# bluz_proto_v2_revA.net
KiCad netlist of a schematic drawn in EAGLE
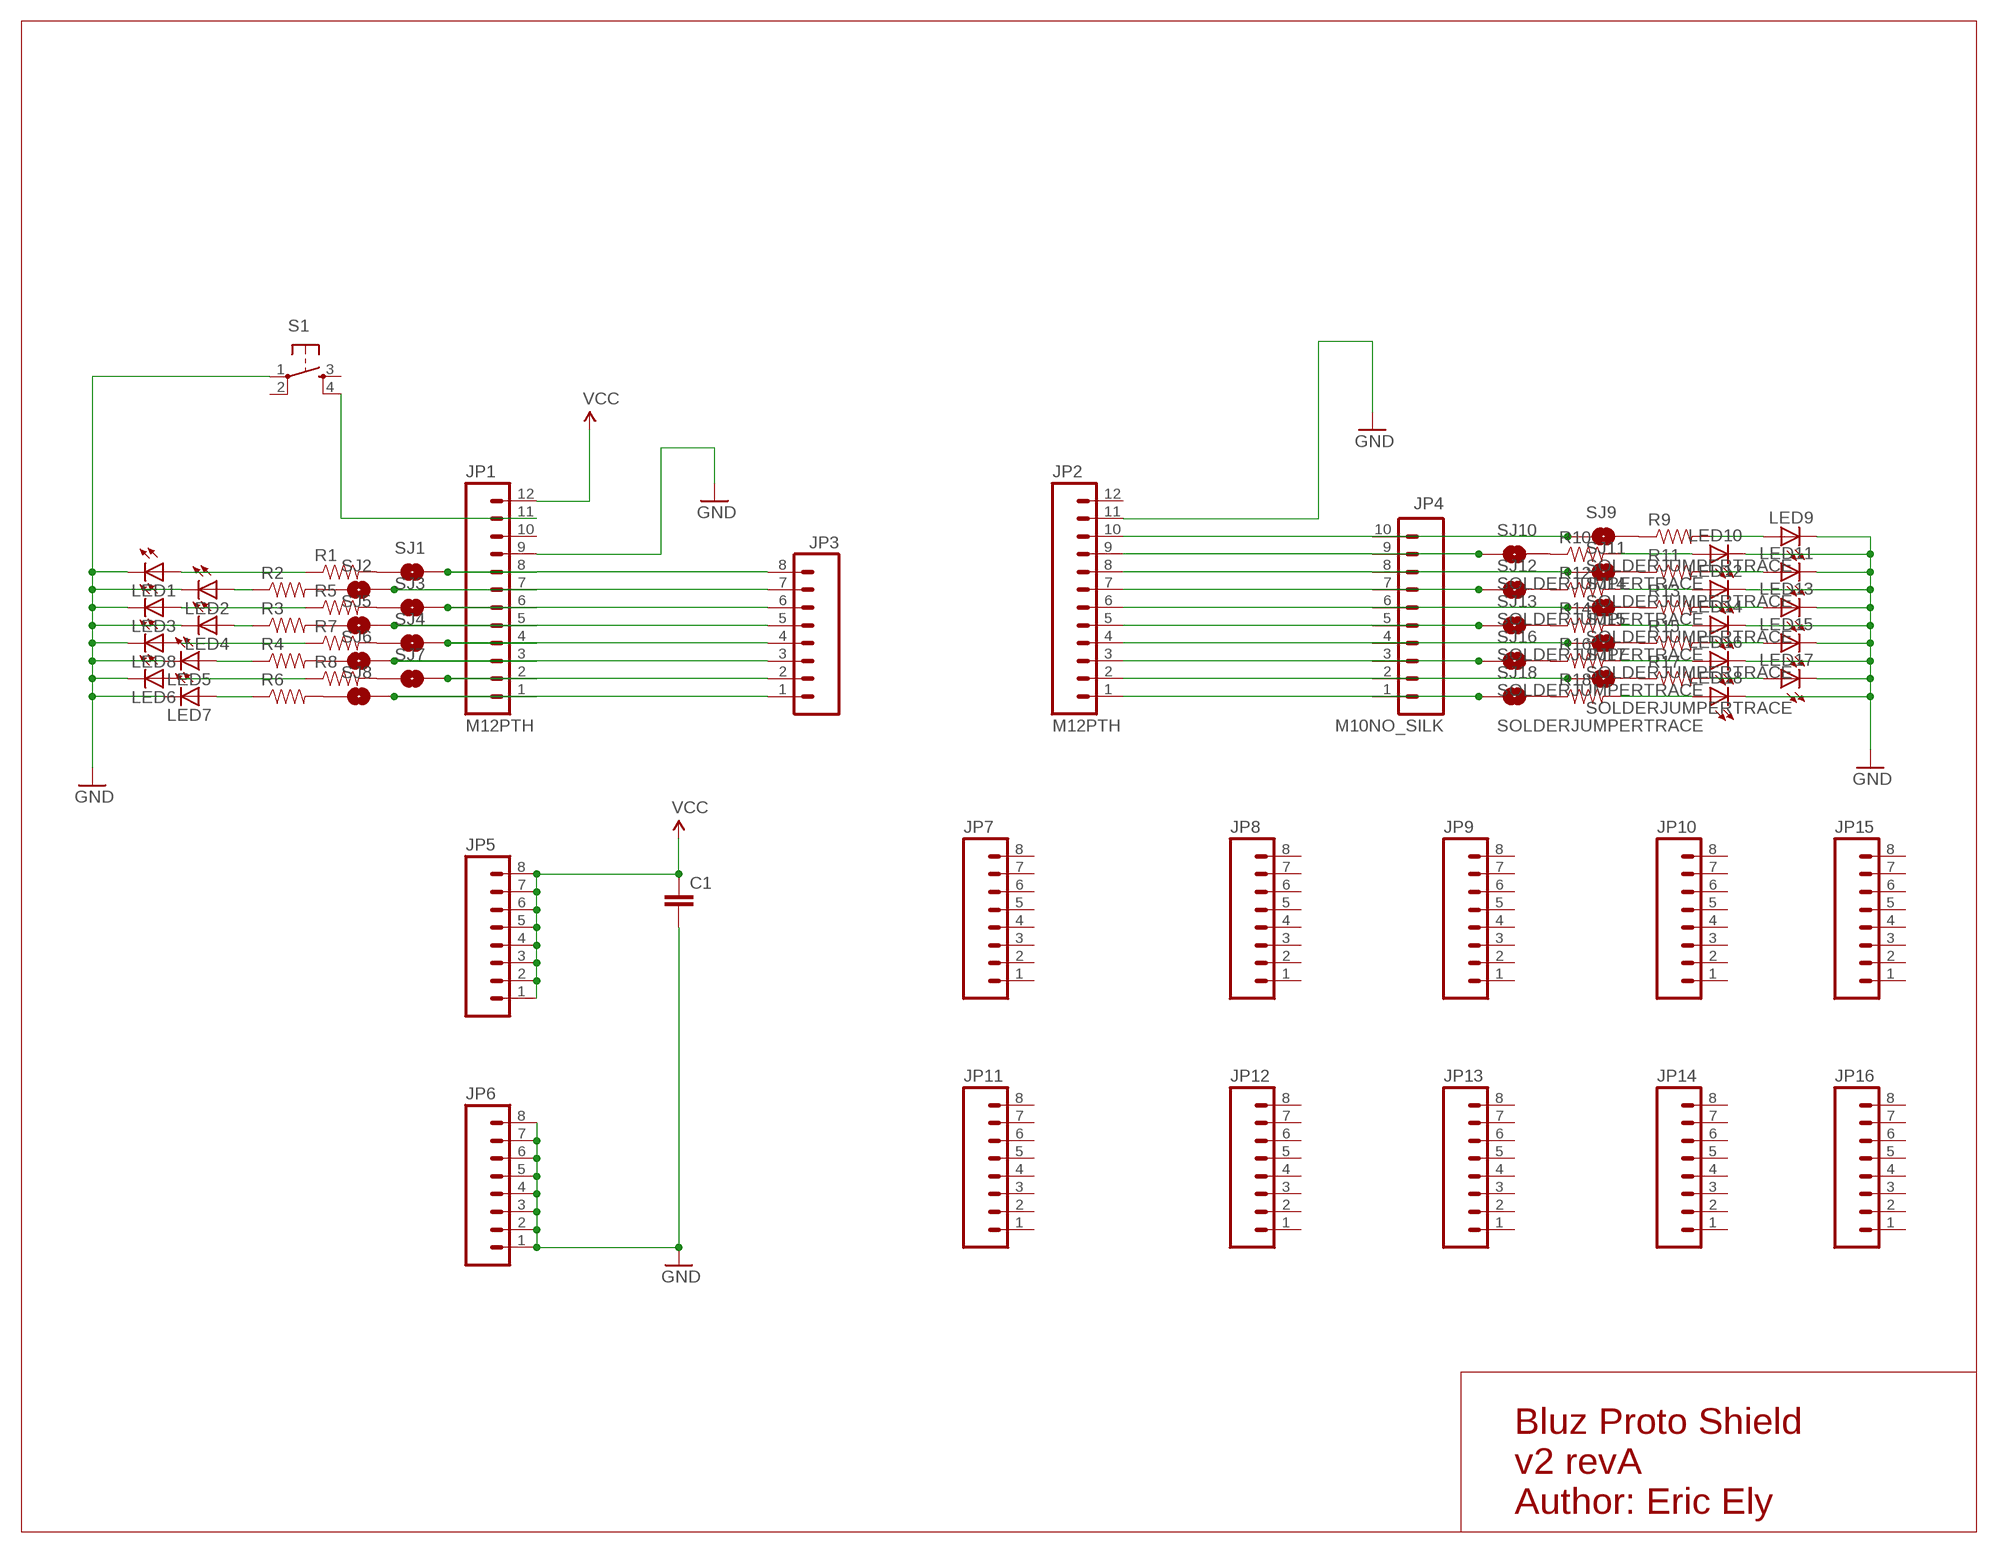
[diagram p0: schematic, sheet 1]

(export (version "E")
  (design (tool "Eeschema 10.0.6"))
  (components
    (comp (ref "C1")
      (value "CAP0603-CAP")
      (footprint "eagle-import:0603-CAP")
      (libsource (lib "eagle-import") (part "CAP0603-CAP"))
    )
    (comp (ref "JP1")
      (value "M12PTH")
      (footprint "eagle-import:1X12")
      (libsource (lib "eagle-import") (part "M12PTH"))
    )
    (comp (ref "JP2")
      (value "M12PTH")
      (footprint "eagle-import:1X12")
      (libsource (lib "eagle-import") (part "M12PTH"))
    )
    (comp (ref "JP3")
      (value "M08NO_SILK")
      (footprint "eagle-import:1X08_NO_SILK")
      (libsource (lib "eagle-import") (part "M08NO_SILK"))
    )
    (comp (ref "JP4")
      (value "M10NO_SILK")
      (footprint "eagle-import:1X10_NO_SILK")
      (libsource (lib "eagle-import") (part "M10NO_SILK"))
    )
    (comp (ref "JP5")
      (value "M08NO_SILK")
      (footprint "eagle-import:1X08_NO_SILK")
      (libsource (lib "eagle-import") (part "M08NO_SILK"))
    )
    (comp (ref "JP6")
      (value "M08NO_SILK")
      (footprint "eagle-import:1X08_NO_SILK")
      (libsource (lib "eagle-import") (part "M08NO_SILK"))
    )
    (comp (ref "JP7")
      (value "M08NO_SILK")
      (footprint "eagle-import:1X08_NO_SILK")
      (libsource (lib "eagle-import") (part "M08NO_SILK"))
    )
    (comp (ref "JP8")
      (value "M08NO_SILK")
      (footprint "eagle-import:1X08_NO_SILK")
      (libsource (lib "eagle-import") (part "M08NO_SILK"))
    )
    (comp (ref "JP9")
      (value "M08NO_SILK")
      (footprint "eagle-import:1X08_NO_SILK")
      (libsource (lib "eagle-import") (part "M08NO_SILK"))
    )
    (comp (ref "JP10")
      (value "M08NO_SILK")
      (footprint "eagle-import:1X08_NO_SILK")
      (libsource (lib "eagle-import") (part "M08NO_SILK"))
    )
    (comp (ref "JP11")
      (value "M08NO_SILK")
      (footprint "eagle-import:1X08_NO_SILK")
      (libsource (lib "eagle-import") (part "M08NO_SILK"))
    )
    (comp (ref "JP12")
      (value "M08NO_SILK")
      (footprint "eagle-import:1X08_NO_SILK")
      (libsource (lib "eagle-import") (part "M08NO_SILK"))
    )
    (comp (ref "JP13")
      (value "M08NO_SILK")
      (footprint "eagle-import:1X08_NO_SILK")
      (libsource (lib "eagle-import") (part "M08NO_SILK"))
    )
    (comp (ref "JP14")
      (value "M08NO_SILK")
      (footprint "eagle-import:1X08_NO_SILK")
      (libsource (lib "eagle-import") (part "M08NO_SILK"))
    )
    (comp (ref "JP15")
      (value "M08NO_SILK")
      (footprint "eagle-import:1X08_NO_SILK")
      (libsource (lib "eagle-import") (part "M08NO_SILK"))
    )
    (comp (ref "JP16")
      (value "M08NO_SILK")
      (footprint "eagle-import:1X08_NO_SILK")
      (libsource (lib "eagle-import") (part "M08NO_SILK"))
    )
    (comp (ref "LED1")
      (value "LEDCHIP-LED0603")
      (footprint "eagle-import:CHIP-LED0603")
      (libsource (lib "eagle-import") (part "LEDCHIP-LED0603"))
    )
    (comp (ref "LED2")
      (value "LEDCHIP-LED0603")
      (footprint "eagle-import:CHIP-LED0603")
      (libsource (lib "eagle-import") (part "LEDCHIP-LED0603"))
    )
    (comp (ref "LED3")
      (value "LEDCHIP-LED0603")
      (footprint "eagle-import:CHIP-LED0603")
      (libsource (lib "eagle-import") (part "LEDCHIP-LED0603"))
    )
    (comp (ref "LED4")
      (value "LEDCHIP-LED0603")
      (footprint "eagle-import:CHIP-LED0603")
      (libsource (lib "eagle-import") (part "LEDCHIP-LED0603"))
    )
    (comp (ref "LED5")
      (value "LEDCHIP-LED0603")
      (footprint "eagle-import:CHIP-LED0603")
      (libsource (lib "eagle-import") (part "LEDCHIP-LED0603"))
    )
    (comp (ref "LED6")
      (value "LEDCHIP-LED0603")
      (footprint "eagle-import:CHIP-LED0603")
      (libsource (lib "eagle-import") (part "LEDCHIP-LED0603"))
    )
    (comp (ref "LED7")
      (value "LEDCHIP-LED0603")
      (footprint "eagle-import:CHIP-LED0603")
      (libsource (lib "eagle-import") (part "LEDCHIP-LED0603"))
    )
    (comp (ref "LED8")
      (value "LEDCHIP-LED0603")
      (footprint "eagle-import:CHIP-LED0603")
      (libsource (lib "eagle-import") (part "LEDCHIP-LED0603"))
    )
    (comp (ref "LED9")
      (value "LEDCHIP-LED0603")
      (footprint "eagle-import:CHIP-LED0603")
      (libsource (lib "eagle-import") (part "LEDCHIP-LED0603"))
    )
    (comp (ref "LED10")
      (value "LEDCHIP-LED0603")
      (footprint "eagle-import:CHIP-LED0603")
      (libsource (lib "eagle-import") (part "LEDCHIP-LED0603"))
    )
    (comp (ref "LED11")
      (value "LEDCHIP-LED0603")
      (footprint "eagle-import:CHIP-LED0603")
      (libsource (lib "eagle-import") (part "LEDCHIP-LED0603"))
    )
    (comp (ref "LED12")
      (value "LEDCHIP-LED0603")
      (footprint "eagle-import:CHIP-LED0603")
      (libsource (lib "eagle-import") (part "LEDCHIP-LED0603"))
    )
    (comp (ref "LED13")
      (value "LEDCHIP-LED0603")
      (footprint "eagle-import:CHIP-LED0603")
      (libsource (lib "eagle-import") (part "LEDCHIP-LED0603"))
    )
    (comp (ref "LED14")
      (value "LEDCHIP-LED0603")
      (footprint "eagle-import:CHIP-LED0603")
      (libsource (lib "eagle-import") (part "LEDCHIP-LED0603"))
    )
    (comp (ref "LED15")
      (value "LEDCHIP-LED0603")
      (footprint "eagle-import:CHIP-LED0603")
      (libsource (lib "eagle-import") (part "LEDCHIP-LED0603"))
    )
    (comp (ref "LED16")
      (value "LEDCHIP-LED0603")
      (footprint "eagle-import:CHIP-LED0603")
      (libsource (lib "eagle-import") (part "LEDCHIP-LED0603"))
    )
    (comp (ref "LED17")
      (value "LEDCHIP-LED0603")
      (footprint "eagle-import:CHIP-LED0603")
      (libsource (lib "eagle-import") (part "LEDCHIP-LED0603"))
    )
    (comp (ref "LED18")
      (value "LEDCHIP-LED0603")
      (footprint "eagle-import:CHIP-LED0603")
      (libsource (lib "eagle-import") (part "LEDCHIP-LED0603"))
    )
    (comp (ref "R1")
      (value "RESISTOR0603-RES")
      (footprint "eagle-import:0603-RES")
      (libsource (lib "eagle-import") (part "RESISTOR0603-RES"))
    )
    (comp (ref "R2")
      (value "RESISTOR0603-RES")
      (footprint "eagle-import:0603-RES")
      (libsource (lib "eagle-import") (part "RESISTOR0603-RES"))
    )
    (comp (ref "R3")
      (value "RESISTOR0603-RES")
      (footprint "eagle-import:0603-RES")
      (libsource (lib "eagle-import") (part "RESISTOR0603-RES"))
    )
    (comp (ref "R4")
      (value "RESISTOR0603-RES")
      (footprint "eagle-import:0603-RES")
      (libsource (lib "eagle-import") (part "RESISTOR0603-RES"))
    )
    (comp (ref "R5")
      (value "RESISTOR0603-RES")
      (footprint "eagle-import:0603-RES")
      (libsource (lib "eagle-import") (part "RESISTOR0603-RES"))
    )
    (comp (ref "R6")
      (value "RESISTOR0603-RES")
      (footprint "eagle-import:0603-RES")
      (libsource (lib "eagle-import") (part "RESISTOR0603-RES"))
    )
    (comp (ref "R7")
      (value "RESISTOR0603-RES")
      (footprint "eagle-import:0603-RES")
      (libsource (lib "eagle-import") (part "RESISTOR0603-RES"))
    )
    (comp (ref "R8")
      (value "RESISTOR0603-RES")
      (footprint "eagle-import:0603-RES")
      (libsource (lib "eagle-import") (part "RESISTOR0603-RES"))
    )
    (comp (ref "R9")
      (value "RESISTOR0603-RES")
      (footprint "eagle-import:0603-RES")
      (libsource (lib "eagle-import") (part "RESISTOR0603-RES"))
    )
    (comp (ref "R10")
      (value "RESISTOR0603-RES")
      (footprint "eagle-import:0603-RES")
      (libsource (lib "eagle-import") (part "RESISTOR0603-RES"))
    )
    (comp (ref "R11")
      (value "RESISTOR0603-RES")
      (footprint "eagle-import:0603-RES")
      (libsource (lib "eagle-import") (part "RESISTOR0603-RES"))
    )
    (comp (ref "R12")
      (value "RESISTOR0603-RES")
      (footprint "eagle-import:0603-RES")
      (libsource (lib "eagle-import") (part "RESISTOR0603-RES"))
    )
    (comp (ref "R13")
      (value "RESISTOR0603-RES")
      (footprint "eagle-import:0603-RES")
      (libsource (lib "eagle-import") (part "RESISTOR0603-RES"))
    )
    (comp (ref "R14")
      (value "RESISTOR0603-RES")
      (footprint "eagle-import:0603-RES")
      (libsource (lib "eagle-import") (part "RESISTOR0603-RES"))
    )
    (comp (ref "R15")
      (value "RESISTOR0603-RES")
      (footprint "eagle-import:0603-RES")
      (libsource (lib "eagle-import") (part "RESISTOR0603-RES"))
    )
    (comp (ref "R16")
      (value "RESISTOR0603-RES")
      (footprint "eagle-import:0603-RES")
      (libsource (lib "eagle-import") (part "RESISTOR0603-RES"))
    )
    (comp (ref "R17")
      (value "RESISTOR0603-RES")
      (footprint "eagle-import:0603-RES")
      (libsource (lib "eagle-import") (part "RESISTOR0603-RES"))
    )
    (comp (ref "R18")
      (value "RESISTOR0603-RES")
      (footprint "eagle-import:0603-RES")
      (libsource (lib "eagle-import") (part "RESISTOR0603-RES"))
    )
    (comp (ref "S1")
      (value "TAC_SWITCHSMD")
      (footprint "eagle-import:TACTILE_SWITCH_SMD")
      (libsource (lib "eagle-import") (part "TAC_SWITCHSMD"))
    )
    (comp (ref "SJ1")
      (value "SOLDERJUMPERTRACE")
      (footprint "eagle-import:SJ_2S-TRACE")
      (libsource (lib "eagle-import") (part "SOLDERJUMPERTRACE"))
    )
    (comp (ref "SJ2")
      (value "SOLDERJUMPERTRACE")
      (footprint "eagle-import:SJ_2S-TRACE")
      (libsource (lib "eagle-import") (part "SOLDERJUMPERTRACE"))
    )
    (comp (ref "SJ3")
      (value "SOLDERJUMPERTRACE")
      (footprint "eagle-import:SJ_2S-TRACE")
      (libsource (lib "eagle-import") (part "SOLDERJUMPERTRACE"))
    )
    (comp (ref "SJ4")
      (value "SOLDERJUMPERTRACE")
      (footprint "eagle-import:SJ_2S-TRACE")
      (libsource (lib "eagle-import") (part "SOLDERJUMPERTRACE"))
    )
    (comp (ref "SJ5")
      (value "SOLDERJUMPERTRACE")
      (footprint "eagle-import:SJ_2S-TRACE")
      (libsource (lib "eagle-import") (part "SOLDERJUMPERTRACE"))
    )
    (comp (ref "SJ6")
      (value "SOLDERJUMPERTRACE")
      (footprint "eagle-import:SJ_2S-TRACE")
      (libsource (lib "eagle-import") (part "SOLDERJUMPERTRACE"))
    )
    (comp (ref "SJ7")
      (value "SOLDERJUMPERTRACE")
      (footprint "eagle-import:SJ_2S-TRACE")
      (libsource (lib "eagle-import") (part "SOLDERJUMPERTRACE"))
    )
    (comp (ref "SJ8")
      (value "SOLDERJUMPERTRACE")
      (footprint "eagle-import:SJ_2S-TRACE")
      (libsource (lib "eagle-import") (part "SOLDERJUMPERTRACE"))
    )
    (comp (ref "SJ9")
      (value "SOLDERJUMPERTRACE")
      (footprint "eagle-import:SJ_2S-TRACE")
      (libsource (lib "eagle-import") (part "SOLDERJUMPERTRACE"))
    )
    (comp (ref "SJ10")
      (value "SOLDERJUMPERTRACE")
      (footprint "eagle-import:SJ_2S-TRACE")
      (libsource (lib "eagle-import") (part "SOLDERJUMPERTRACE"))
    )
    (comp (ref "SJ11")
      (value "SOLDERJUMPERTRACE")
      (footprint "eagle-import:SJ_2S-TRACE")
      (libsource (lib "eagle-import") (part "SOLDERJUMPERTRACE"))
    )
    (comp (ref "SJ12")
      (value "SOLDERJUMPERTRACE")
      (footprint "eagle-import:SJ_2S-TRACE")
      (libsource (lib "eagle-import") (part "SOLDERJUMPERTRACE"))
    )
    (comp (ref "SJ13")
      (value "SOLDERJUMPERTRACE")
      (footprint "eagle-import:SJ_2S-TRACE")
      (libsource (lib "eagle-import") (part "SOLDERJUMPERTRACE"))
    )
    (comp (ref "SJ14")
      (value "SOLDERJUMPERTRACE")
      (footprint "eagle-import:SJ_2S-TRACE")
      (libsource (lib "eagle-import") (part "SOLDERJUMPERTRACE"))
    )
    (comp (ref "SJ15")
      (value "SOLDERJUMPERTRACE")
      (footprint "eagle-import:SJ_2S-TRACE")
      (libsource (lib "eagle-import") (part "SOLDERJUMPERTRACE"))
    )
    (comp (ref "SJ16")
      (value "SOLDERJUMPERTRACE")
      (footprint "eagle-import:SJ_2S-TRACE")
      (libsource (lib "eagle-import") (part "SOLDERJUMPERTRACE"))
    )
    (comp (ref "SJ17")
      (value "SOLDERJUMPERTRACE")
      (footprint "eagle-import:SJ_2S-TRACE")
      (libsource (lib "eagle-import") (part "SOLDERJUMPERTRACE"))
    )
    (comp (ref "SJ18")
      (value "SOLDERJUMPERTRACE")
      (footprint "eagle-import:SJ_2S-TRACE")
      (libsource (lib "eagle-import") (part "SOLDERJUMPERTRACE"))
    )
  )
  (nets
    (net (code "1") (name "GND") (class "Default")
      (node (ref "C1") (pin "2") (pinfunction "2_2") (pintype "passive"))
      (node (ref "JP1") (pin "9") (pinfunction "9_9") (pintype "passive"))
      (node (ref "JP2") (pin "11") (pinfunction "11_11") (pintype "passive"))
      (node (ref "JP6") (pin "1") (pinfunction "1_1") (pintype "passive"))
      (node (ref "JP6") (pin "2") (pinfunction "2_2") (pintype "passive"))
      (node (ref "JP6") (pin "3") (pinfunction "3_3") (pintype "passive"))
      (node (ref "JP6") (pin "4") (pinfunction "4_4") (pintype "passive"))
      (node (ref "JP6") (pin "5") (pinfunction "5_5") (pintype "passive"))
      (node (ref "JP6") (pin "6") (pinfunction "6_6") (pintype "passive"))
      (node (ref "JP6") (pin "7") (pinfunction "7_7") (pintype "passive"))
      (node (ref "JP6") (pin "8") (pinfunction "8_8") (pintype "passive"))
      (node (ref "LED1") (pin "C") (pinfunction "C_C") (pintype "passive"))
      (node (ref "LED10") (pin "C") (pinfunction "C_C") (pintype "passive"))
      (node (ref "LED11") (pin "C") (pinfunction "C_C") (pintype "passive"))
      (node (ref "LED12") (pin "C") (pinfunction "C_C") (pintype "passive"))
      (node (ref "LED13") (pin "C") (pinfunction "C_C") (pintype "passive"))
      (node (ref "LED14") (pin "C") (pinfunction "C_C") (pintype "passive"))
      (node (ref "LED15") (pin "C") (pinfunction "C_C") (pintype "passive"))
      (node (ref "LED16") (pin "C") (pinfunction "C_C") (pintype "passive"))
      (node (ref "LED17") (pin "C") (pinfunction "C_C") (pintype "passive"))
      (node (ref "LED18") (pin "C") (pinfunction "C_C") (pintype "passive"))
      (node (ref "LED2") (pin "C") (pinfunction "C_C") (pintype "passive"))
      (node (ref "LED3") (pin "C") (pinfunction "C_C") (pintype "passive"))
      (node (ref "LED4") (pin "C") (pinfunction "C_C") (pintype "passive"))
      (node (ref "LED5") (pin "C") (pinfunction "C_C") (pintype "passive"))
      (node (ref "LED6") (pin "C") (pinfunction "C_C") (pintype "passive"))
      (node (ref "LED7") (pin "C") (pinfunction "C_C") (pintype "passive"))
      (node (ref "LED8") (pin "C") (pinfunction "C_C") (pintype "passive"))
      (node (ref "LED9") (pin "C") (pinfunction "C_C") (pintype "passive"))
      (node (ref "S1") (pin "1") (pinfunction "1_1") (pintype "passive"))
    )
    (net (code "2") (name "Net-(JP1-Pad1)") (class "Default")
      (node (ref "JP1") (pin "1") (pinfunction "1_1") (pintype "passive"))
      (node (ref "JP3") (pin "1") (pinfunction "1_1") (pintype "passive"))
      (node (ref "SJ8") (pin "2") (pinfunction "2_2") (pintype "passive"))
    )
    (net (code "3") (name "Net-(JP1-Pad2)") (class "Default")
      (node (ref "JP1") (pin "2") (pinfunction "2_2") (pintype "passive"))
      (node (ref "JP3") (pin "2") (pinfunction "2_2") (pintype "passive"))
      (node (ref "SJ7") (pin "2") (pinfunction "2_2") (pintype "passive"))
    )
    (net (code "4") (name "Net-(JP1-Pad3)") (class "Default")
      (node (ref "JP1") (pin "3") (pinfunction "3_3") (pintype "passive"))
      (node (ref "JP3") (pin "3") (pinfunction "3_3") (pintype "passive"))
      (node (ref "SJ6") (pin "2") (pinfunction "2_2") (pintype "passive"))
    )
    (net (code "5") (name "Net-(JP1-Pad4)") (class "Default")
      (node (ref "JP1") (pin "4") (pinfunction "4_4") (pintype "passive"))
      (node (ref "JP3") (pin "4") (pinfunction "4_4") (pintype "passive"))
      (node (ref "SJ4") (pin "2") (pinfunction "2_2") (pintype "passive"))
    )
    (net (code "6") (name "Net-(JP1-Pad5)") (class "Default")
      (node (ref "JP1") (pin "5") (pinfunction "5_5") (pintype "passive"))
      (node (ref "JP3") (pin "5") (pinfunction "5_5") (pintype "passive"))
      (node (ref "SJ5") (pin "2") (pinfunction "2_2") (pintype "passive"))
    )
    (net (code "7") (name "Net-(JP1-Pad6)") (class "Default")
      (node (ref "JP1") (pin "6") (pinfunction "6_6") (pintype "passive"))
      (node (ref "JP3") (pin "6") (pinfunction "6_6") (pintype "passive"))
      (node (ref "SJ3") (pin "2") (pinfunction "2_2") (pintype "passive"))
    )
    (net (code "8") (name "Net-(JP1-Pad7)") (class "Default")
      (node (ref "JP1") (pin "7") (pinfunction "7_7") (pintype "passive"))
      (node (ref "JP3") (pin "7") (pinfunction "7_7") (pintype "passive"))
      (node (ref "SJ2") (pin "2") (pinfunction "2_2") (pintype "passive"))
    )
    (net (code "9") (name "Net-(JP1-Pad8)") (class "Default")
      (node (ref "JP1") (pin "8") (pinfunction "8_8") (pintype "passive"))
      (node (ref "JP3") (pin "8") (pinfunction "8_8") (pintype "passive"))
      (node (ref "SJ1") (pin "2") (pinfunction "2_2") (pintype "passive"))
    )
    (net (code "10") (name "Net-(JP1-Pad11)") (class "Default")
      (node (ref "JP1") (pin "11") (pinfunction "11_11") (pintype "passive"))
      (node (ref "S1") (pin "4") (pinfunction "4_4") (pintype "passive"))
    )
    (net (code "11") (name "Net-(JP2-Pad1)") (class "Default")
      (node (ref "JP2") (pin "1") (pinfunction "1_1") (pintype "passive"))
      (node (ref "JP4") (pin "1") (pinfunction "1_1") (pintype "passive"))
      (node (ref "SJ18") (pin "1") (pinfunction "1_1") (pintype "passive"))
    )
    (net (code "12") (name "Net-(JP2-Pad2)") (class "Default")
      (node (ref "JP2") (pin "2") (pinfunction "2_2") (pintype "passive"))
      (node (ref "JP4") (pin "2") (pinfunction "2_2") (pintype "passive"))
      (node (ref "SJ17") (pin "1") (pinfunction "1_1") (pintype "passive"))
    )
    (net (code "13") (name "Net-(JP2-Pad3)") (class "Default")
      (node (ref "JP2") (pin "3") (pinfunction "3_3") (pintype "passive"))
      (node (ref "JP4") (pin "3") (pinfunction "3_3") (pintype "passive"))
      (node (ref "SJ16") (pin "1") (pinfunction "1_1") (pintype "passive"))
    )
    (net (code "14") (name "Net-(JP2-Pad4)") (class "Default")
      (node (ref "JP2") (pin "4") (pinfunction "4_4") (pintype "passive"))
      (node (ref "JP4") (pin "4") (pinfunction "4_4") (pintype "passive"))
      (node (ref "SJ15") (pin "1") (pinfunction "1_1") (pintype "passive"))
    )
    (net (code "15") (name "Net-(JP2-Pad5)") (class "Default")
      (node (ref "JP2") (pin "5") (pinfunction "5_5") (pintype "passive"))
      (node (ref "JP4") (pin "5") (pinfunction "5_5") (pintype "passive"))
      (node (ref "SJ13") (pin "1") (pinfunction "1_1") (pintype "passive"))
    )
    (net (code "16") (name "Net-(JP2-Pad6)") (class "Default")
      (node (ref "JP2") (pin "6") (pinfunction "6_6") (pintype "passive"))
      (node (ref "JP4") (pin "6") (pinfunction "6_6") (pintype "passive"))
      (node (ref "SJ14") (pin "1") (pinfunction "1_1") (pintype "passive"))
    )
    (net (code "17") (name "Net-(JP2-Pad7)") (class "Default")
      (node (ref "JP2") (pin "7") (pinfunction "7_7") (pintype "passive"))
      (node (ref "JP4") (pin "7") (pinfunction "7_7") (pintype "passive"))
      (node (ref "SJ12") (pin "1") (pinfunction "1_1") (pintype "passive"))
    )
    (net (code "18") (name "Net-(JP2-Pad8)") (class "Default")
      (node (ref "JP2") (pin "8") (pinfunction "8_8") (pintype "passive"))
      (node (ref "JP4") (pin "8") (pinfunction "8_8") (pintype "passive"))
      (node (ref "SJ11") (pin "1") (pinfunction "1_1") (pintype "passive"))
    )
    (net (code "19") (name "Net-(JP2-Pad9)") (class "Default")
      (node (ref "JP2") (pin "9") (pinfunction "9_9") (pintype "passive"))
      (node (ref "JP4") (pin "9") (pinfunction "9_9") (pintype "passive"))
      (node (ref "SJ10") (pin "1") (pinfunction "1_1") (pintype "passive"))
    )
    (net (code "20") (name "Net-(JP2-Pad10)") (class "Default")
      (node (ref "JP2") (pin "10") (pinfunction "10_10") (pintype "passive"))
      (node (ref "JP4") (pin "10") (pinfunction "10_10") (pintype "passive"))
      (node (ref "SJ9") (pin "1") (pinfunction "1_1") (pintype "passive"))
    )
    (net (code "21") (name "Net-(LED1-PadA)") (class "Default")
      (node (ref "LED1") (pin "A") (pinfunction "A_A") (pintype "passive"))
      (node (ref "R1") (pin "1") (pinfunction "1_1") (pintype "passive"))
    )
    (net (code "22") (name "Net-(LED2-PadA)") (class "Default")
      (node (ref "LED2") (pin "A") (pinfunction "A_A") (pintype "passive"))
      (node (ref "R2") (pin "1") (pinfunction "1_1") (pintype "passive"))
    )
    (net (code "23") (name "Net-(LED3-PadA)") (class "Default")
      (node (ref "LED3") (pin "A") (pinfunction "A_A") (pintype "passive"))
      (node (ref "R5") (pin "1") (pinfunction "1_1") (pintype "passive"))
    )
    (net (code "24") (name "Net-(LED4-PadA)") (class "Default")
      (node (ref "LED4") (pin "A") (pinfunction "A_A") (pintype "passive"))
      (node (ref "R3") (pin "1") (pinfunction "1_1") (pintype "passive"))
    )
    (net (code "25") (name "Net-(LED5-PadA)") (class "Default")
      (node (ref "LED5") (pin "A") (pinfunction "A_A") (pintype "passive"))
      (node (ref "R4") (pin "1") (pinfunction "1_1") (pintype "passive"))
    )
    (net (code "26") (name "Net-(LED6-PadA)") (class "Default")
      (node (ref "LED6") (pin "A") (pinfunction "A_A") (pintype "passive"))
      (node (ref "R8") (pin "1") (pinfunction "1_1") (pintype "passive"))
    )
    (net (code "27") (name "Net-(LED7-PadA)") (class "Default")
      (node (ref "LED7") (pin "A") (pinfunction "A_A") (pintype "passive"))
      (node (ref "R6") (pin "1") (pinfunction "1_1") (pintype "passive"))
    )
    (net (code "28") (name "Net-(LED8-PadA)") (class "Default")
      (node (ref "LED8") (pin "A") (pinfunction "A_A") (pintype "passive"))
      (node (ref "R7") (pin "1") (pinfunction "1_1") (pintype "passive"))
    )
    (net (code "29") (name "Net-(LED9-PadA)") (class "Default")
      (node (ref "LED9") (pin "A") (pinfunction "A_A") (pintype "passive"))
      (node (ref "R9") (pin "2") (pinfunction "2_2") (pintype "passive"))
    )
    (net (code "30") (name "Net-(LED10-PadA)") (class "Default")
      (node (ref "LED10") (pin "A") (pinfunction "A_A") (pintype "passive"))
      (node (ref "R10") (pin "2") (pinfunction "2_2") (pintype "passive"))
    )
    (net (code "31") (name "Net-(LED11-PadA)") (class "Default")
      (node (ref "LED11") (pin "A") (pinfunction "A_A") (pintype "passive"))
      (node (ref "R11") (pin "2") (pinfunction "2_2") (pintype "passive"))
    )
    (net (code "32") (name "Net-(LED12-PadA)") (class "Default")
      (node (ref "LED12") (pin "A") (pinfunction "A_A") (pintype "passive"))
      (node (ref "R12") (pin "2") (pinfunction "2_2") (pintype "passive"))
    )
    (net (code "33") (name "Net-(LED13-PadA)") (class "Default")
      (node (ref "LED13") (pin "A") (pinfunction "A_A") (pintype "passive"))
      (node (ref "R13") (pin "2") (pinfunction "2_2") (pintype "passive"))
    )
    (net (code "34") (name "Net-(LED14-PadA)") (class "Default")
      (node (ref "LED14") (pin "A") (pinfunction "A_A") (pintype "passive"))
      (node (ref "R14") (pin "2") (pinfunction "2_2") (pintype "passive"))
    )
    (net (code "35") (name "Net-(LED15-PadA)") (class "Default")
      (node (ref "LED15") (pin "A") (pinfunction "A_A") (pintype "passive"))
      (node (ref "R15") (pin "2") (pinfunction "2_2") (pintype "passive"))
    )
    (net (code "36") (name "Net-(LED16-PadA)") (class "Default")
      (node (ref "LED16") (pin "A") (pinfunction "A_A") (pintype "passive"))
      (node (ref "R16") (pin "2") (pinfunction "2_2") (pintype "passive"))
    )
    (net (code "37") (name "Net-(LED17-PadA)") (class "Default")
      (node (ref "LED17") (pin "A") (pinfunction "A_A") (pintype "passive"))
      (node (ref "R17") (pin "2") (pinfunction "2_2") (pintype "passive"))
    )
    (net (code "38") (name "Net-(LED18-PadA)") (class "Default")
      (node (ref "LED18") (pin "A") (pinfunction "A_A") (pintype "passive"))
      (node (ref "R18") (pin "2") (pinfunction "2_2") (pintype "passive"))
    )
    (net (code "39") (name "Net-(R1-Pad2)") (class "Default")
      (node (ref "R1") (pin "2") (pinfunction "2_2") (pintype "passive"))
      (node (ref "SJ1") (pin "1") (pinfunction "1_1") (pintype "passive"))
    )
    (net (code "40") (name "Net-(R2-Pad2)") (class "Default")
      (node (ref "R2") (pin "2") (pinfunction "2_2") (pintype "passive"))
      (node (ref "SJ2") (pin "1") (pinfunction "1_1") (pintype "passive"))
    )
    (net (code "41") (name "Net-(R3-Pad2)") (class "Default")
      (node (ref "R3") (pin "2") (pinfunction "2_2") (pintype "passive"))
      (node (ref "SJ5") (pin "1") (pinfunction "1_1") (pintype "passive"))
    )
    (net (code "42") (name "Net-(R4-Pad2)") (class "Default")
      (node (ref "R4") (pin "2") (pinfunction "2_2") (pintype "passive"))
      (node (ref "SJ6") (pin "1") (pinfunction "1_1") (pintype "passive"))
    )
    (net (code "43") (name "Net-(R5-Pad2)") (class "Default")
      (node (ref "R5") (pin "2") (pinfunction "2_2") (pintype "passive"))
      (node (ref "SJ3") (pin "1") (pinfunction "1_1") (pintype "passive"))
    )
    (net (code "44") (name "Net-(R6-Pad2)") (class "Default")
      (node (ref "R6") (pin "2") (pinfunction "2_2") (pintype "passive"))
      (node (ref "SJ8") (pin "1") (pinfunction "1_1") (pintype "passive"))
    )
    (net (code "45") (name "Net-(R7-Pad2)") (class "Default")
      (node (ref "R7") (pin "2") (pinfunction "2_2") (pintype "passive"))
      (node (ref "SJ4") (pin "1") (pinfunction "1_1") (pintype "passive"))
    )
    (net (code "46") (name "Net-(R8-Pad2)") (class "Default")
      (node (ref "R8") (pin "2") (pinfunction "2_2") (pintype "passive"))
      (node (ref "SJ7") (pin "1") (pinfunction "1_1") (pintype "passive"))
    )
    (net (code "47") (name "Net-(R9-Pad1)") (class "Default")
      (node (ref "R9") (pin "1") (pinfunction "1_1") (pintype "passive"))
      (node (ref "SJ9") (pin "2") (pinfunction "2_2") (pintype "passive"))
    )
    (net (code "48") (name "Net-(R10-Pad1)") (class "Default")
      (node (ref "R10") (pin "1") (pinfunction "1_1") (pintype "passive"))
      (node (ref "SJ10") (pin "2") (pinfunction "2_2") (pintype "passive"))
    )
    (net (code "49") (name "Net-(R11-Pad1)") (class "Default")
      (node (ref "R11") (pin "1") (pinfunction "1_1") (pintype "passive"))
      (node (ref "SJ11") (pin "2") (pinfunction "2_2") (pintype "passive"))
    )
    (net (code "50") (name "Net-(R12-Pad1)") (class "Default")
      (node (ref "R12") (pin "1") (pinfunction "1_1") (pintype "passive"))
      (node (ref "SJ12") (pin "2") (pinfunction "2_2") (pintype "passive"))
    )
    (net (code "51") (name "Net-(R13-Pad1)") (class "Default")
      (node (ref "R13") (pin "1") (pinfunction "1_1") (pintype "passive"))
      (node (ref "SJ14") (pin "2") (pinfunction "2_2") (pintype "passive"))
    )
    (net (code "52") (name "Net-(R14-Pad1)") (class "Default")
      (node (ref "R14") (pin "1") (pinfunction "1_1") (pintype "passive"))
      (node (ref "SJ13") (pin "2") (pinfunction "2_2") (pintype "passive"))
    )
    (net (code "53") (name "Net-(R15-Pad1)") (class "Default")
      (node (ref "R15") (pin "1") (pinfunction "1_1") (pintype "passive"))
      (node (ref "SJ15") (pin "2") (pinfunction "2_2") (pintype "passive"))
    )
    (net (code "54") (name "Net-(R16-Pad1)") (class "Default")
      (node (ref "R16") (pin "1") (pinfunction "1_1") (pintype "passive"))
      (node (ref "SJ16") (pin "2") (pinfunction "2_2") (pintype "passive"))
    )
    (net (code "55") (name "Net-(R17-Pad1)") (class "Default")
      (node (ref "R17") (pin "1") (pinfunction "1_1") (pintype "passive"))
      (node (ref "SJ17") (pin "2") (pinfunction "2_2") (pintype "passive"))
    )
    (net (code "56") (name "Net-(R18-Pad1)") (class "Default")
      (node (ref "R18") (pin "1") (pinfunction "1_1") (pintype "passive"))
      (node (ref "SJ18") (pin "2") (pinfunction "2_2") (pintype "passive"))
    )
    (net (code "57") (name "VCC") (class "Default")
      (node (ref "C1") (pin "1") (pinfunction "1_1") (pintype "passive"))
      (node (ref "JP1") (pin "12") (pinfunction "12_12") (pintype "passive"))
      (node (ref "JP5") (pin "1") (pinfunction "1_1") (pintype "passive"))
      (node (ref "JP5") (pin "2") (pinfunction "2_2") (pintype "passive"))
      (node (ref "JP5") (pin "3") (pinfunction "3_3") (pintype "passive"))
      (node (ref "JP5") (pin "4") (pinfunction "4_4") (pintype "passive"))
      (node (ref "JP5") (pin "5") (pinfunction "5_5") (pintype "passive"))
      (node (ref "JP5") (pin "6") (pinfunction "6_6") (pintype "passive"))
      (node (ref "JP5") (pin "7") (pinfunction "7_7") (pintype "passive"))
      (node (ref "JP5") (pin "8") (pinfunction "8_8") (pintype "passive"))
    )
    (net (code "58") (name "unconnected-(JP1-Pad10)") (class "Default")
      (node (ref "JP1") (pin "10") (pinfunction "10_10") (pintype "passive"))
    )
    (net (code "59") (name "unconnected-(JP2-Pad12)") (class "Default")
      (node (ref "JP2") (pin "12") (pinfunction "12_12") (pintype "passive"))
    )
    (net (code "60") (name "unconnected-(JP7-Pad1)") (class "Default")
      (node (ref "JP7") (pin "1") (pinfunction "1_1") (pintype "passive"))
    )
    (net (code "61") (name "unconnected-(JP7-Pad2)") (class "Default")
      (node (ref "JP7") (pin "2") (pinfunction "2_2") (pintype "passive"))
    )
    (net (code "62") (name "unconnected-(JP7-Pad3)") (class "Default")
      (node (ref "JP7") (pin "3") (pinfunction "3_3") (pintype "passive"))
    )
    (net (code "63") (name "unconnected-(JP7-Pad4)") (class "Default")
      (node (ref "JP7") (pin "4") (pinfunction "4_4") (pintype "passive"))
    )
    (net (code "64") (name "unconnected-(JP7-Pad5)") (class "Default")
      (node (ref "JP7") (pin "5") (pinfunction "5_5") (pintype "passive"))
    )
    (net (code "65") (name "unconnected-(JP7-Pad6)") (class "Default")
      (node (ref "JP7") (pin "6") (pinfunction "6_6") (pintype "passive"))
    )
    (net (code "66") (name "unconnected-(JP7-Pad7)") (class "Default")
      (node (ref "JP7") (pin "7") (pinfunction "7_7") (pintype "passive"))
    )
    (net (code "67") (name "unconnected-(JP7-Pad8)") (class "Default")
      (node (ref "JP7") (pin "8") (pinfunction "8_8") (pintype "passive"))
    )
    (net (code "68") (name "unconnected-(JP8-Pad1)") (class "Default")
      (node (ref "JP8") (pin "1") (pinfunction "1_1") (pintype "passive"))
    )
    (net (code "69") (name "unconnected-(JP8-Pad2)") (class "Default")
      (node (ref "JP8") (pin "2") (pinfunction "2_2") (pintype "passive"))
    )
    (net (code "70") (name "unconnected-(JP8-Pad3)") (class "Default")
      (node (ref "JP8") (pin "3") (pinfunction "3_3") (pintype "passive"))
    )
    (net (code "71") (name "unconnected-(JP8-Pad4)") (class "Default")
      (node (ref "JP8") (pin "4") (pinfunction "4_4") (pintype "passive"))
    )
    (net (code "72") (name "unconnected-(JP8-Pad5)") (class "Default")
      (node (ref "JP8") (pin "5") (pinfunction "5_5") (pintype "passive"))
    )
    (net (code "73") (name "unconnected-(JP8-Pad6)") (class "Default")
      (node (ref "JP8") (pin "6") (pinfunction "6_6") (pintype "passive"))
    )
    (net (code "74") (name "unconnected-(JP8-Pad7)") (class "Default")
      (node (ref "JP8") (pin "7") (pinfunction "7_7") (pintype "passive"))
    )
    (net (code "75") (name "unconnected-(JP8-Pad8)") (class "Default")
      (node (ref "JP8") (pin "8") (pinfunction "8_8") (pintype "passive"))
    )
    (net (code "76") (name "unconnected-(JP9-Pad1)") (class "Default")
      (node (ref "JP9") (pin "1") (pinfunction "1_1") (pintype "passive"))
    )
    (net (code "77") (name "unconnected-(JP9-Pad2)") (class "Default")
      (node (ref "JP9") (pin "2") (pinfunction "2_2") (pintype "passive"))
    )
    (net (code "78") (name "unconnected-(JP9-Pad3)") (class "Default")
      (node (ref "JP9") (pin "3") (pinfunction "3_3") (pintype "passive"))
    )
    (net (code "79") (name "unconnected-(JP9-Pad4)") (class "Default")
      (node (ref "JP9") (pin "4") (pinfunction "4_4") (pintype "passive"))
    )
    (net (code "80") (name "unconnected-(JP9-Pad5)") (class "Default")
      (node (ref "JP9") (pin "5") (pinfunction "5_5") (pintype "passive"))
    )
    (net (code "81") (name "unconnected-(JP9-Pad6)") (class "Default")
      (node (ref "JP9") (pin "6") (pinfunction "6_6") (pintype "passive"))
    )
    (net (code "82") (name "unconnected-(JP9-Pad7)") (class "Default")
      (node (ref "JP9") (pin "7") (pinfunction "7_7") (pintype "passive"))
    )
    (net (code "83") (name "unconnected-(JP9-Pad8)") (class "Default")
      (node (ref "JP9") (pin "8") (pinfunction "8_8") (pintype "passive"))
    )
    (net (code "84") (name "unconnected-(JP10-Pad1)") (class "Default")
      (node (ref "JP10") (pin "1") (pinfunction "1_1") (pintype "passive"))
    )
    (net (code "85") (name "unconnected-(JP10-Pad2)") (class "Default")
      (node (ref "JP10") (pin "2") (pinfunction "2_2") (pintype "passive"))
    )
    (net (code "86") (name "unconnected-(JP10-Pad3)") (class "Default")
      (node (ref "JP10") (pin "3") (pinfunction "3_3") (pintype "passive"))
    )
    (net (code "87") (name "unconnected-(JP10-Pad4)") (class "Default")
      (node (ref "JP10") (pin "4") (pinfunction "4_4") (pintype "passive"))
    )
    (net (code "88") (name "unconnected-(JP10-Pad5)") (class "Default")
      (node (ref "JP10") (pin "5") (pinfunction "5_5") (pintype "passive"))
    )
    (net (code "89") (name "unconnected-(JP10-Pad6)") (class "Default")
      (node (ref "JP10") (pin "6") (pinfunction "6_6") (pintype "passive"))
    )
    (net (code "90") (name "unconnected-(JP10-Pad7)") (class "Default")
      (node (ref "JP10") (pin "7") (pinfunction "7_7") (pintype "passive"))
    )
    (net (code "91") (name "unconnected-(JP10-Pad8)") (class "Default")
      (node (ref "JP10") (pin "8") (pinfunction "8_8") (pintype "passive"))
    )
    (net (code "92") (name "unconnected-(JP11-Pad1)") (class "Default")
      (node (ref "JP11") (pin "1") (pinfunction "1_1") (pintype "passive"))
    )
    (net (code "93") (name "unconnected-(JP11-Pad2)") (class "Default")
      (node (ref "JP11") (pin "2") (pinfunction "2_2") (pintype "passive"))
    )
    (net (code "94") (name "unconnected-(JP11-Pad3)") (class "Default")
      (node (ref "JP11") (pin "3") (pinfunction "3_3") (pintype "passive"))
    )
    (net (code "95") (name "unconnected-(JP11-Pad4)") (class "Default")
      (node (ref "JP11") (pin "4") (pinfunction "4_4") (pintype "passive"))
    )
    (net (code "96") (name "unconnected-(JP11-Pad5)") (class "Default")
      (node (ref "JP11") (pin "5") (pinfunction "5_5") (pintype "passive"))
    )
    (net (code "97") (name "unconnected-(JP11-Pad6)") (class "Default")
      (node (ref "JP11") (pin "6") (pinfunction "6_6") (pintype "passive"))
    )
    (net (code "98") (name "unconnected-(JP11-Pad7)") (class "Default")
      (node (ref "JP11") (pin "7") (pinfunction "7_7") (pintype "passive"))
    )
    (net (code "99") (name "unconnected-(JP11-Pad8)") (class "Default")
      (node (ref "JP11") (pin "8") (pinfunction "8_8") (pintype "passive"))
    )
    (net (code "100") (name "unconnected-(JP12-Pad1)") (class "Default")
      (node (ref "JP12") (pin "1") (pinfunction "1_1") (pintype "passive"))
    )
    (net (code "101") (name "unconnected-(JP12-Pad2)") (class "Default")
      (node (ref "JP12") (pin "2") (pinfunction "2_2") (pintype "passive"))
    )
    (net (code "102") (name "unconnected-(JP12-Pad3)") (class "Default")
      (node (ref "JP12") (pin "3") (pinfunction "3_3") (pintype "passive"))
    )
    (net (code "103") (name "unconnected-(JP12-Pad4)") (class "Default")
      (node (ref "JP12") (pin "4") (pinfunction "4_4") (pintype "passive"))
    )
    (net (code "104") (name "unconnected-(JP12-Pad5)") (class "Default")
      (node (ref "JP12") (pin "5") (pinfunction "5_5") (pintype "passive"))
    )
    (net (code "105") (name "unconnected-(JP12-Pad6)") (class "Default")
      (node (ref "JP12") (pin "6") (pinfunction "6_6") (pintype "passive"))
    )
    (net (code "106") (name "unconnected-(JP12-Pad7)") (class "Default")
      (node (ref "JP12") (pin "7") (pinfunction "7_7") (pintype "passive"))
    )
    (net (code "107") (name "unconnected-(JP12-Pad8)") (class "Default")
      (node (ref "JP12") (pin "8") (pinfunction "8_8") (pintype "passive"))
    )
    (net (code "108") (name "unconnected-(JP13-Pad1)") (class "Default")
      (node (ref "JP13") (pin "1") (pinfunction "1_1") (pintype "passive"))
    )
    (net (code "109") (name "unconnected-(JP13-Pad2)") (class "Default")
      (node (ref "JP13") (pin "2") (pinfunction "2_2") (pintype "passive"))
    )
    (net (code "110") (name "unconnected-(JP13-Pad3)") (class "Default")
      (node (ref "JP13") (pin "3") (pinfunction "3_3") (pintype "passive"))
    )
    (net (code "111") (name "unconnected-(JP13-Pad4)") (class "Default")
      (node (ref "JP13") (pin "4") (pinfunction "4_4") (pintype "passive"))
    )
    (net (code "112") (name "unconnected-(JP13-Pad5)") (class "Default")
      (node (ref "JP13") (pin "5") (pinfunction "5_5") (pintype "passive"))
    )
    (net (code "113") (name "unconnected-(JP13-Pad6)") (class "Default")
      (node (ref "JP13") (pin "6") (pinfunction "6_6") (pintype "passive"))
    )
    (net (code "114") (name "unconnected-(JP13-Pad7)") (class "Default")
      (node (ref "JP13") (pin "7") (pinfunction "7_7") (pintype "passive"))
    )
    (net (code "115") (name "unconnected-(JP13-Pad8)") (class "Default")
      (node (ref "JP13") (pin "8") (pinfunction "8_8") (pintype "passive"))
    )
    (net (code "116") (name "unconnected-(JP14-Pad1)") (class "Default")
      (node (ref "JP14") (pin "1") (pinfunction "1_1") (pintype "passive"))
    )
    (net (code "117") (name "unconnected-(JP14-Pad2)") (class "Default")
      (node (ref "JP14") (pin "2") (pinfunction "2_2") (pintype "passive"))
    )
    (net (code "118") (name "unconnected-(JP14-Pad3)") (class "Default")
      (node (ref "JP14") (pin "3") (pinfunction "3_3") (pintype "passive"))
    )
    (net (code "119") (name "unconnected-(JP14-Pad4)") (class "Default")
      (node (ref "JP14") (pin "4") (pinfunction "4_4") (pintype "passive"))
    )
    (net (code "120") (name "unconnected-(JP14-Pad5)") (class "Default")
      (node (ref "JP14") (pin "5") (pinfunction "5_5") (pintype "passive"))
    )
    (net (code "121") (name "unconnected-(JP14-Pad6)") (class "Default")
      (node (ref "JP14") (pin "6") (pinfunction "6_6") (pintype "passive"))
    )
    (net (code "122") (name "unconnected-(JP14-Pad7)") (class "Default")
      (node (ref "JP14") (pin "7") (pinfunction "7_7") (pintype "passive"))
    )
    (net (code "123") (name "unconnected-(JP14-Pad8)") (class "Default")
      (node (ref "JP14") (pin "8") (pinfunction "8_8") (pintype "passive"))
    )
    (net (code "124") (name "unconnected-(JP15-Pad1)") (class "Default")
      (node (ref "JP15") (pin "1") (pinfunction "1_1") (pintype "passive"))
    )
    (net (code "125") (name "unconnected-(JP15-Pad2)") (class "Default")
      (node (ref "JP15") (pin "2") (pinfunction "2_2") (pintype "passive"))
    )
    (net (code "126") (name "unconnected-(JP15-Pad3)") (class "Default")
      (node (ref "JP15") (pin "3") (pinfunction "3_3") (pintype "passive"))
    )
    (net (code "127") (name "unconnected-(JP15-Pad4)") (class "Default")
      (node (ref "JP15") (pin "4") (pinfunction "4_4") (pintype "passive"))
    )
    (net (code "128") (name "unconnected-(JP15-Pad5)") (class "Default")
      (node (ref "JP15") (pin "5") (pinfunction "5_5") (pintype "passive"))
    )
    (net (code "129") (name "unconnected-(JP15-Pad6)") (class "Default")
      (node (ref "JP15") (pin "6") (pinfunction "6_6") (pintype "passive"))
    )
    (net (code "130") (name "unconnected-(JP15-Pad7)") (class "Default")
      (node (ref "JP15") (pin "7") (pinfunction "7_7") (pintype "passive"))
    )
    (net (code "131") (name "unconnected-(JP15-Pad8)") (class "Default")
      (node (ref "JP15") (pin "8") (pinfunction "8_8") (pintype "passive"))
    )
    (net (code "132") (name "unconnected-(JP16-Pad1)") (class "Default")
      (node (ref "JP16") (pin "1") (pinfunction "1_1") (pintype "passive"))
    )
    (net (code "133") (name "unconnected-(JP16-Pad2)") (class "Default")
      (node (ref "JP16") (pin "2") (pinfunction "2_2") (pintype "passive"))
    )
    (net (code "134") (name "unconnected-(JP16-Pad3)") (class "Default")
      (node (ref "JP16") (pin "3") (pinfunction "3_3") (pintype "passive"))
    )
    (net (code "135") (name "unconnected-(JP16-Pad4)") (class "Default")
      (node (ref "JP16") (pin "4") (pinfunction "4_4") (pintype "passive"))
    )
    (net (code "136") (name "unconnected-(JP16-Pad5)") (class "Default")
      (node (ref "JP16") (pin "5") (pinfunction "5_5") (pintype "passive"))
    )
    (net (code "137") (name "unconnected-(JP16-Pad6)") (class "Default")
      (node (ref "JP16") (pin "6") (pinfunction "6_6") (pintype "passive"))
    )
    (net (code "138") (name "unconnected-(JP16-Pad7)") (class "Default")
      (node (ref "JP16") (pin "7") (pinfunction "7_7") (pintype "passive"))
    )
    (net (code "139") (name "unconnected-(JP16-Pad8)") (class "Default")
      (node (ref "JP16") (pin "8") (pinfunction "8_8") (pintype "passive"))
    )
    (net (code "140") (name "unconnected-(S1-Pad2)") (class "Default")
      (node (ref "S1") (pin "2") (pinfunction "2_2") (pintype "passive"))
    )
    (net (code "141") (name "unconnected-(S1-Pad3)") (class "Default")
      (node (ref "S1") (pin "3") (pinfunction "3_3") (pintype "passive"))
    )
  )
)
